# esp32-template.net
KiCad netlist of a schematic drawn in EAGLE
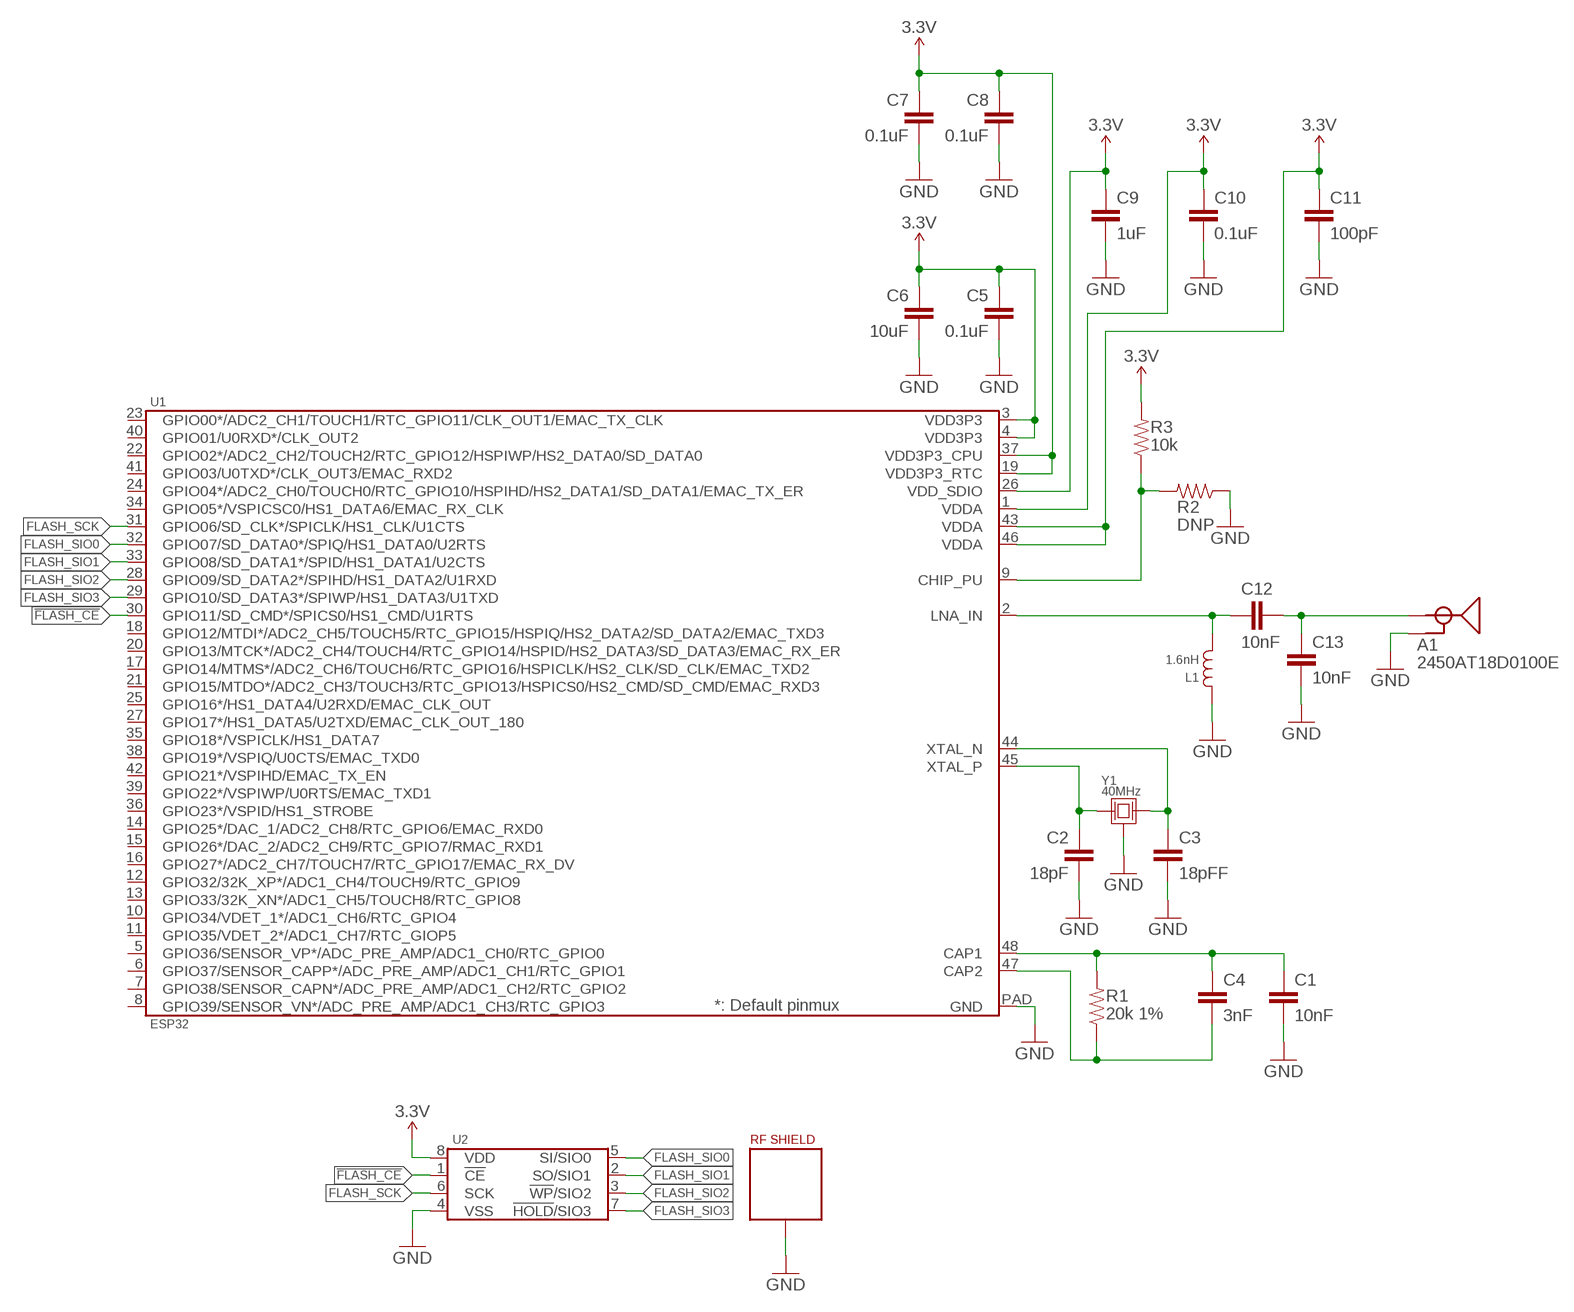
[diagram p0: schematic, sheet 1]

(export (version "E")
  (design (tool "Eeschema 10.0.6"))
  (components
    (comp (ref "A1")
      (value "2450AT18D0100E")
      (footprint "eagle-import:4SMD-ANTENNA")
      (libsource (lib "eagle-import") (part "2450AT18D0100E"))
    )
    (comp (ref "C1")
      (value "10nF")
      (footprint "eagle-import:0603-CAP")
      (libsource (lib "eagle-import") (part "CAP-0603"))
    )
    (comp (ref "C2")
      (value "18pF")
      (footprint "eagle-import:0603-CAP")
      (libsource (lib "eagle-import") (part "CAP-0603"))
    )
    (comp (ref "C3")
      (value "18pFF")
      (footprint "eagle-import:0603-CAP")
      (libsource (lib "eagle-import") (part "CAP-0603"))
    )
    (comp (ref "C4")
      (value "3nF")
      (footprint "eagle-import:0603-CAP")
      (libsource (lib "eagle-import") (part "CAP-0603"))
    )
    (comp (ref "C5")
      (value "0.1uF")
      (footprint "eagle-import:0603-CAP")
      (libsource (lib "eagle-import") (part "CAP-0603"))
    )
    (comp (ref "C6")
      (value "10uF")
      (footprint "eagle-import:0603-CAP")
      (libsource (lib "eagle-import") (part "CAP-0603"))
    )
    (comp (ref "C7")
      (value "0.1uF")
      (footprint "eagle-import:0603-CAP")
      (libsource (lib "eagle-import") (part "CAP-0603"))
    )
    (comp (ref "C8")
      (value "0.1uF")
      (footprint "eagle-import:0603-CAP")
      (libsource (lib "eagle-import") (part "CAP-0603"))
    )
    (comp (ref "C9")
      (value "1uF")
      (footprint "eagle-import:0603-CAP")
      (libsource (lib "eagle-import") (part "CAP-0603"))
    )
    (comp (ref "C10")
      (value "0.1uF")
      (footprint "eagle-import:0603-CAP")
      (libsource (lib "eagle-import") (part "CAP-0603"))
    )
    (comp (ref "C11")
      (value "100pF")
      (footprint "eagle-import:0603-CAP")
      (libsource (lib "eagle-import") (part "CAP-0603"))
    )
    (comp (ref "C12")
      (value "10nF")
      (footprint "eagle-import:0603-CAP")
      (libsource (lib "eagle-import") (part "CAP-0603"))
    )
    (comp (ref "C13")
      (value "10nF")
      (footprint "eagle-import:0603-CAP")
      (libsource (lib "eagle-import") (part "CAP-0603"))
    )
    (comp (ref "L1")
      (value "1.6nH")
      (footprint "eagle-import:0603-FERRITE")
      (libsource (lib "eagle-import") (part "INDUCTOR-0603"))
    )
    (comp (ref "R1")
      (value "20k 1%")
      (footprint "eagle-import:0603-CAP")
      (libsource (lib "eagle-import") (part "RESISTOR-0603"))
    )
    (comp (ref "R2")
      (value "DNP")
      (footprint "eagle-import:0603-CAP")
      (libsource (lib "eagle-import") (part "RESISTOR-0603"))
    )
    (comp (ref "R3")
      (value "10k")
      (footprint "eagle-import:0603-CAP")
      (libsource (lib "eagle-import") (part "RESISTOR-0603"))
    )
    (comp (ref "U$1")
      (value "RF-SHIELD")
      (footprint "eagle-import:RF_SHIELD-.65X.65")
      (libsource (lib "eagle-import") (part "RF-SHIELD"))
    )
    (comp (ref "U1")
      (value "ESP32")
      (footprint "eagle-import:ESP32")
      (libsource (lib "eagle-import") (part "ESP32"))
    )
    (comp (ref "U2")
      (value "FLASH-USON")
      (footprint "eagle-import:USON-8-2X3")
      (libsource (lib "eagle-import") (part "FLASH-USON"))
    )
    (comp (ref "Y1")
      (value "40MHz")
      (footprint "eagle-import:FA-238")
      (libsource (lib "eagle-import") (part "CRYSTAL-3.2X2.5"))
    )
  )
  (nets
    (net (code "1") (name "/~{FLASH_CE}") (class "Default")
      (node (ref "U1") (pin "30") (pinfunction "GPIO11/SD_CMD*/SPICS0/HS1_CMD/U1RTS_30") (pintype "bidirectional"))
      (node (ref "U2") (pin "1") (pinfunction "~{CE}_1") (pintype "bidirectional"))
    )
    (net (code "2") (name "3.3V") (class "Default")
      (node (ref "C10") (pin "1") (pinfunction "1_1") (pintype "passive"))
      (node (ref "C11") (pin "1") (pinfunction "1_1") (pintype "passive"))
      (node (ref "C5") (pin "1") (pinfunction "1_1") (pintype "passive"))
      (node (ref "C6") (pin "1") (pinfunction "1_1") (pintype "passive"))
      (node (ref "C7") (pin "1") (pinfunction "1_1") (pintype "passive"))
      (node (ref "C8") (pin "1") (pinfunction "1_1") (pintype "passive"))
      (node (ref "C9") (pin "1") (pinfunction "1_1") (pintype "passive"))
      (node (ref "R3") (pin "2") (pinfunction "2_2") (pintype "passive"))
      (node (ref "U1") (pin "1") (pinfunction "VDDA_1") (pintype "bidirectional"))
      (node (ref "U1") (pin "19") (pinfunction "VDD3P3_RTC_19") (pintype "bidirectional"))
      (node (ref "U1") (pin "26") (pinfunction "VDD_SDIO_26") (pintype "bidirectional"))
      (node (ref "U1") (pin "3") (pinfunction "VDD3P3_3") (pintype "bidirectional"))
      (node (ref "U1") (pin "37") (pinfunction "VDD3P3_CPU_37") (pintype "bidirectional"))
      (node (ref "U1") (pin "4") (pinfunction "VDD3P3_4") (pintype "bidirectional"))
      (node (ref "U1") (pin "43") (pinfunction "VDDA_43") (pintype "bidirectional"))
      (node (ref "U1") (pin "46") (pinfunction "VDDA_46") (pintype "bidirectional"))
      (node (ref "U2") (pin "8") (pinfunction "VDD_8") (pintype "bidirectional"))
    )
    (net (code "3") (name "FLASH_SCK") (class "Default")
      (node (ref "U1") (pin "31") (pinfunction "GPIO06/SD_CLK*/SPICLK/HS1_CLK/U1CTS_31") (pintype "bidirectional"))
      (node (ref "U2") (pin "6") (pinfunction "SCK_6") (pintype "bidirectional"))
    )
    (net (code "4") (name "FLASH_SIO0") (class "Default")
      (node (ref "U1") (pin "32") (pinfunction "GPIO07/SD_DATA0*/SPIQ/HS1_DATA0/U2RTS_32") (pintype "bidirectional"))
      (node (ref "U2") (pin "5") (pinfunction "SI/SIO0_5") (pintype "bidirectional"))
    )
    (net (code "5") (name "FLASH_SIO1") (class "Default")
      (node (ref "U1") (pin "33") (pinfunction "GPIO08/SD_DATA1*/SPID/HS1_DATA1/U2CTS_33") (pintype "bidirectional"))
      (node (ref "U2") (pin "2") (pinfunction "SO/SIO1_2") (pintype "bidirectional"))
    )
    (net (code "6") (name "FLASH_SIO2") (class "Default")
      (node (ref "U1") (pin "28") (pinfunction "GPIO09/SD_DATA2*/SPIHD/HS1_DATA2/U1RXD_28") (pintype "bidirectional"))
      (node (ref "U2") (pin "3") (pinfunction "~{WP}/SIO2_3") (pintype "bidirectional"))
    )
    (net (code "7") (name "FLASH_SIO3") (class "Default")
      (node (ref "U1") (pin "29") (pinfunction "GPIO10/SD_DATA3*/SPIWP/HS1_DATA3/U1TXD_29") (pintype "bidirectional"))
      (node (ref "U2") (pin "7") (pinfunction "~{HOLD}/SIO3_7") (pintype "bidirectional"))
    )
    (net (code "8") (name "GND") (class "Default")
      (node (ref "A1") (pin "2") (pinfunction "GND_2") (pintype "bidirectional"))
      (node (ref "A1") (pin "3") (pinfunction "GND_3") (pintype "bidirectional"))
      (node (ref "A1") (pin "4") (pinfunction "GND_4") (pintype "bidirectional"))
      (node (ref "C1") (pin "2") (pinfunction "2_2") (pintype "passive"))
      (node (ref "C10") (pin "2") (pinfunction "2_2") (pintype "passive"))
      (node (ref "C11") (pin "2") (pinfunction "2_2") (pintype "passive"))
      (node (ref "C13") (pin "2") (pinfunction "2_2") (pintype "passive"))
      (node (ref "C2") (pin "2") (pinfunction "2_2") (pintype "passive"))
      (node (ref "C3") (pin "2") (pinfunction "2_2") (pintype "passive"))
      (node (ref "C5") (pin "2") (pinfunction "2_2") (pintype "passive"))
      (node (ref "C6") (pin "2") (pinfunction "2_2") (pintype "passive"))
      (node (ref "C7") (pin "2") (pinfunction "2_2") (pintype "passive"))
      (node (ref "C8") (pin "2") (pinfunction "2_2") (pintype "passive"))
      (node (ref "C9") (pin "2") (pinfunction "2_2") (pintype "passive"))
      (node (ref "L1") (pin "P$1") (pinfunction "P$1_P$1") (pintype "bidirectional"))
      (node (ref "R2") (pin "1") (pinfunction "1_1") (pintype "passive"))
      (node (ref "U$1") (pin "P$1") (pinfunction "P$1_P$1") (pintype "bidirectional"))
      (node (ref "U$1") (pin "P$10") (pinfunction "P$1_P$10") (pintype "bidirectional"))
      (node (ref "U$1") (pin "P$11") (pinfunction "P$1_P$11") (pintype "bidirectional"))
      (node (ref "U$1") (pin "P$12") (pinfunction "P$1_P$12") (pintype "bidirectional"))
      (node (ref "U$1") (pin "P$2") (pinfunction "P$1_P$2") (pintype "bidirectional"))
      (node (ref "U$1") (pin "P$3") (pinfunction "P$1_P$3") (pintype "bidirectional"))
      (node (ref "U$1") (pin "P$4") (pinfunction "P$1_P$4") (pintype "bidirectional"))
      (node (ref "U$1") (pin "P$5") (pinfunction "P$1_P$5") (pintype "bidirectional"))
      (node (ref "U$1") (pin "P$6") (pinfunction "P$1_P$6") (pintype "bidirectional"))
      (node (ref "U$1") (pin "P$7") (pinfunction "P$1_P$7") (pintype "bidirectional"))
      (node (ref "U$1") (pin "P$8") (pinfunction "P$1_P$8") (pintype "bidirectional"))
      (node (ref "U$1") (pin "P$9") (pinfunction "P$1_P$9") (pintype "bidirectional"))
      (node (ref "U1") (pin "PAD") (pinfunction "GND_PAD") (pintype "bidirectional"))
      (node (ref "U2") (pin "4") (pinfunction "VSS_4") (pintype "bidirectional"))
      (node (ref "Y1") (pin "2") (pinfunction "GND_2") (pintype "bidirectional"))
      (node (ref "Y1") (pin "4") (pinfunction "GND_4") (pintype "bidirectional"))
    )
    (net (code "9") (name "Net-(A1-SIGNAL)") (class "Default")
      (node (ref "A1") (pin "1") (pinfunction "SIGNAL_1") (pintype "bidirectional"))
      (node (ref "C12") (pin "2") (pinfunction "2_2") (pintype "passive"))
      (node (ref "C13") (pin "1") (pinfunction "1_1") (pintype "passive"))
    )
    (net (code "10") (name "Net-(U1-CAP1)") (class "Default")
      (node (ref "C1") (pin "1") (pinfunction "1_1") (pintype "passive"))
      (node (ref "C4") (pin "1") (pinfunction "1_1") (pintype "passive"))
      (node (ref "R1") (pin "2") (pinfunction "2_2") (pintype "passive"))
      (node (ref "U1") (pin "48") (pinfunction "CAP1_48") (pintype "bidirectional"))
    )
    (net (code "11") (name "Net-(U1-CAP2)") (class "Default")
      (node (ref "C4") (pin "2") (pinfunction "2_2") (pintype "passive"))
      (node (ref "R1") (pin "1") (pinfunction "1_1") (pintype "passive"))
      (node (ref "U1") (pin "47") (pinfunction "CAP2_47") (pintype "bidirectional"))
    )
    (net (code "12") (name "Net-(U1-CHIP_PU)") (class "Default")
      (node (ref "R2") (pin "2") (pinfunction "2_2") (pintype "passive"))
      (node (ref "R3") (pin "1") (pinfunction "1_1") (pintype "passive"))
      (node (ref "U1") (pin "9") (pinfunction "CHIP_PU_9") (pintype "bidirectional"))
    )
    (net (code "13") (name "Net-(U1-LNA_IN)") (class "Default")
      (node (ref "C12") (pin "1") (pinfunction "1_1") (pintype "passive"))
      (node (ref "L1") (pin "P$2") (pinfunction "P$2_P$2") (pintype "bidirectional"))
      (node (ref "U1") (pin "2") (pinfunction "LNA_IN_2") (pintype "bidirectional"))
    )
    (net (code "14") (name "Net-(U1-XTAL_N)") (class "Default")
      (node (ref "C3") (pin "1") (pinfunction "1_1") (pintype "passive"))
      (node (ref "U1") (pin "44") (pinfunction "XTAL_N_44") (pintype "bidirectional"))
      (node (ref "Y1") (pin "3") (pinfunction "2_3") (pintype "bidirectional"))
    )
    (net (code "15") (name "Net-(U1-XTAL_P)") (class "Default")
      (node (ref "C2") (pin "1") (pinfunction "1_1") (pintype "passive"))
      (node (ref "U1") (pin "45") (pinfunction "XTAL_P_45") (pintype "bidirectional"))
      (node (ref "Y1") (pin "1") (pinfunction "1_1") (pintype "bidirectional"))
    )
    (net (code "16") (name "unconnected-(U1-GPIO00*{slash}ADC2_CH1{slash}TOUCH1{slash}RTC_GPIO11{slash}CLK_OUT1{slash}EMAC_TX_CLK-Pad23)") (class "Default")
      (node (ref "U1") (pin "23") (pinfunction "GPIO00*/ADC2_CH1/TOUCH1/RTC_GPIO11/CLK_OUT1/EMAC_TX_CLK_23") (pintype "bidirectional"))
    )
    (net (code "17") (name "unconnected-(U1-GPIO01{slash}U0RXD*{slash}CLK_OUT2-Pad40)") (class "Default")
      (node (ref "U1") (pin "40") (pinfunction "GPIO01/U0RXD*/CLK_OUT2_40") (pintype "bidirectional"))
    )
    (net (code "18") (name "unconnected-(U1-GPIO02*{slash}ADC2_CH2{slash}TOUCH2{slash}RTC_GPIO12{slash}HSPIWP{slash}HS2_DATA0{slash}SD_DATA0-Pad22)") (class "Default")
      (node (ref "U1") (pin "22") (pinfunction "GPIO02*/ADC2_CH2/TOUCH2/RTC_GPIO12/HSPIWP/HS2_DATA0/SD_DATA0_22") (pintype "bidirectional"))
    )
    (net (code "19") (name "unconnected-(U1-GPIO03{slash}U0TXD*{slash}CLK_OUT3{slash}EMAC_RXD2-Pad41)") (class "Default")
      (node (ref "U1") (pin "41") (pinfunction "GPIO03/U0TXD*/CLK_OUT3/EMAC_RXD2_41") (pintype "bidirectional"))
    )
    (net (code "20") (name "unconnected-(U1-GPIO04*{slash}ADC2_CH0{slash}TOUCH0{slash}RTC_GPIO10{slash}HSPIHD{slash}HS2_DATA1{slash}SD_DATA1{slash}EMAC_TX_ER-Pad24)") (class "Default")
      (node (ref "U1") (pin "24") (pinfunction "GPIO04*/ADC2_CH0/TOUCH0/RTC_GPIO10/HSPIHD/HS2_DATA1/SD_DATA1/EMAC_TX_ER_24") (pintype "bidirectional"))
    )
    (net (code "21") (name "unconnected-(U1-GPIO05*{slash}VSPICSC0{slash}HS1_DATA6{slash}EMAC_RX_CLK-Pad34)") (class "Default")
      (node (ref "U1") (pin "34") (pinfunction "GPIO05*/VSPICSC0/HS1_DATA6/EMAC_RX_CLK_34") (pintype "bidirectional"))
    )
    (net (code "22") (name "unconnected-(U1-GPIO12{slash}MTDI*{slash}ADC2_CH5{slash}TOUCH5{slash}RTC_GPIO15{slash}HSPIQ{slash}HS2_DATA2{slash}SD_DATA2{slash}EMAC_TXD3-Pad18)") (class "Default")
      (node (ref "U1") (pin "18") (pinfunction "GPIO12/MTDI*/ADC2_CH5/TOUCH5/RTC_GPIO15/HSPIQ/HS2_DATA2/SD_DATA2/EMAC_TXD3_18") (pintype "bidirectional"))
    )
    (net (code "23") (name "unconnected-(U1-GPIO13{slash}MTCK*{slash}ADC2_CH4{slash}TOUCH4{slash}RTC_GPIO14{slash}HSPID{slash}HS2_DATA3{slash}SD_DATA3{slash}EMAC_RX_ER-Pad20)") (class "Default")
      (node (ref "U1") (pin "20") (pinfunction "GPIO13/MTCK*/ADC2_CH4/TOUCH4/RTC_GPIO14/HSPID/HS2_DATA3/SD_DATA3/EMAC_RX_ER_20") (pintype "bidirectional"))
    )
    (net (code "24") (name "unconnected-(U1-GPIO14{slash}MTMS*{slash}ADC2_CH6{slash}TOUCH6{slash}RTC_GPIO16{slash}HSPICLK{slash}HS2_CLK{slash}SD_CLK{slash}EMAC_TXD2-Pad17)") (class "Default")
      (node (ref "U1") (pin "17") (pinfunction "GPIO14/MTMS*/ADC2_CH6/TOUCH6/RTC_GPIO16/HSPICLK/HS2_CLK/SD_CLK/EMAC_TXD2_17") (pintype "bidirectional"))
    )
    (net (code "25") (name "unconnected-(U1-GPIO15{slash}MTDO*{slash}ADC2_CH3{slash}TOUCH3{slash}RTC_GPIO13{slash}HSPICS0{slash}HS2_CMD{slash}SD_CMD{slash}EMAC_RXD3-Pad21)") (class "Default")
      (node (ref "U1") (pin "21") (pinfunction "GPIO15/MTDO*/ADC2_CH3/TOUCH3/RTC_GPIO13/HSPICS0/HS2_CMD/SD_CMD/EMAC_RXD3_21") (pintype "bidirectional"))
    )
    (net (code "26") (name "unconnected-(U1-GPIO16*{slash}HS1_DATA4{slash}U2RXD{slash}EMAC_CLK_OUT-Pad25)") (class "Default")
      (node (ref "U1") (pin "25") (pinfunction "GPIO16*/HS1_DATA4/U2RXD/EMAC_CLK_OUT_25") (pintype "bidirectional"))
    )
    (net (code "27") (name "unconnected-(U1-GPIO17*{slash}HS1_DATA5{slash}U2TXD{slash}EMAC_CLK_OUT_180-Pad27)") (class "Default")
      (node (ref "U1") (pin "27") (pinfunction "GPIO17*/HS1_DATA5/U2TXD/EMAC_CLK_OUT_180_27") (pintype "bidirectional"))
    )
    (net (code "28") (name "unconnected-(U1-GPIO18*{slash}VSPICLK{slash}HS1_DATA7-Pad35)") (class "Default")
      (node (ref "U1") (pin "35") (pinfunction "GPIO18*/VSPICLK/HS1_DATA7_35") (pintype "bidirectional"))
    )
    (net (code "29") (name "unconnected-(U1-GPIO19*{slash}VSPIQ{slash}U0CTS{slash}EMAC_TXD0-Pad38)") (class "Default")
      (node (ref "U1") (pin "38") (pinfunction "GPIO19*/VSPIQ/U0CTS/EMAC_TXD0_38") (pintype "bidirectional"))
    )
    (net (code "30") (name "unconnected-(U1-GPIO21*{slash}VSPIHD{slash}EMAC_TX_EN-Pad42)") (class "Default")
      (node (ref "U1") (pin "42") (pinfunction "GPIO21*/VSPIHD/EMAC_TX_EN_42") (pintype "bidirectional"))
    )
    (net (code "31") (name "unconnected-(U1-GPIO22*{slash}VSPIWP{slash}U0RTS{slash}EMAC_TXD1-Pad39)") (class "Default")
      (node (ref "U1") (pin "39") (pinfunction "GPIO22*/VSPIWP/U0RTS/EMAC_TXD1_39") (pintype "bidirectional"))
    )
    (net (code "32") (name "unconnected-(U1-GPIO23*{slash}VSPID{slash}HS1_STROBE-Pad36)") (class "Default")
      (node (ref "U1") (pin "36") (pinfunction "GPIO23*/VSPID/HS1_STROBE_36") (pintype "bidirectional"))
    )
    (net (code "33") (name "unconnected-(U1-GPIO25*{slash}DAC_1{slash}ADC2_CH8{slash}RTC_GPIO6{slash}EMAC_RXD0-Pad14)") (class "Default")
      (node (ref "U1") (pin "14") (pinfunction "GPIO25*/DAC_1/ADC2_CH8/RTC_GPIO6/EMAC_RXD0_14") (pintype "bidirectional"))
    )
    (net (code "34") (name "unconnected-(U1-GPIO26*{slash}DAC_2{slash}ADC2_CH9{slash}RTC_GPIO7{slash}RMAC_RXD1-Pad15)") (class "Default")
      (node (ref "U1") (pin "15") (pinfunction "GPIO26*/DAC_2/ADC2_CH9/RTC_GPIO7/RMAC_RXD1_15") (pintype "bidirectional"))
    )
    (net (code "35") (name "unconnected-(U1-GPIO27*{slash}ADC2_CH7{slash}TOUCH7{slash}RTC_GPIO17{slash}EMAC_RX_DV-Pad16)") (class "Default")
      (node (ref "U1") (pin "16") (pinfunction "GPIO27*/ADC2_CH7/TOUCH7/RTC_GPIO17/EMAC_RX_DV_16") (pintype "bidirectional"))
    )
    (net (code "36") (name "unconnected-(U1-GPIO32{slash}32K_XP*{slash}ADC1_CH4{slash}TOUCH9{slash}RTC_GPIO9-Pad12)") (class "Default")
      (node (ref "U1") (pin "12") (pinfunction "GPIO32/32K_XP*/ADC1_CH4/TOUCH9/RTC_GPIO9_12") (pintype "bidirectional"))
    )
    (net (code "37") (name "unconnected-(U1-GPIO33{slash}32K_XN*{slash}ADC1_CH5{slash}TOUCH8{slash}RTC_GPIO8-Pad13)") (class "Default")
      (node (ref "U1") (pin "13") (pinfunction "GPIO33/32K_XN*/ADC1_CH5/TOUCH8/RTC_GPIO8_13") (pintype "bidirectional"))
    )
    (net (code "38") (name "unconnected-(U1-GPIO34{slash}VDET_1*{slash}ADC1_CH6{slash}RTC_GPIO4-Pad10)") (class "Default")
      (node (ref "U1") (pin "10") (pinfunction "GPIO34/VDET_1*/ADC1_CH6/RTC_GPIO4_10") (pintype "bidirectional"))
    )
    (net (code "39") (name "unconnected-(U1-GPIO35{slash}VDET_2*{slash}ADC1_CH7{slash}RTC_GIOP5-Pad11)") (class "Default")
      (node (ref "U1") (pin "11") (pinfunction "GPIO35/VDET_2*/ADC1_CH7/RTC_GIOP5_11") (pintype "bidirectional"))
    )
    (net (code "40") (name "unconnected-(U1-GPIO36{slash}SENSOR_VP*{slash}ADC_PRE_AMP{slash}ADC1_CH0{slash}RTC_GPIO0-Pad5)") (class "Default")
      (node (ref "U1") (pin "5") (pinfunction "GPIO36/SENSOR_VP*/ADC_PRE_AMP/ADC1_CH0/RTC_GPIO0_5") (pintype "bidirectional"))
    )
    (net (code "41") (name "unconnected-(U1-GPIO37{slash}SENSOR_CAPP*{slash}ADC_PRE_AMP{slash}ADC1_CH1{slash}RTC_GPIO1-Pad6)") (class "Default")
      (node (ref "U1") (pin "6") (pinfunction "GPIO37/SENSOR_CAPP*/ADC_PRE_AMP/ADC1_CH1/RTC_GPIO1_6") (pintype "bidirectional"))
    )
    (net (code "42") (name "unconnected-(U1-GPIO38{slash}SENSOR_CAPN*{slash}ADC_PRE_AMP{slash}ADC1_CH2{slash}RTC_GPIO2-Pad7)") (class "Default")
      (node (ref "U1") (pin "7") (pinfunction "GPIO38/SENSOR_CAPN*/ADC_PRE_AMP/ADC1_CH2/RTC_GPIO2_7") (pintype "bidirectional"))
    )
    (net (code "43") (name "unconnected-(U1-GPIO39{slash}SENSOR_VN*{slash}ADC_PRE_AMP{slash}ADC1_CH3{slash}RTC_GPIO3-Pad8)") (class "Default")
      (node (ref "U1") (pin "8") (pinfunction "GPIO39/SENSOR_VN*/ADC_PRE_AMP/ADC1_CH3/RTC_GPIO3_8") (pintype "bidirectional"))
    )
  )
)
